# eHub.net
KiCad netlist of a schematic drawn in Altium Designer
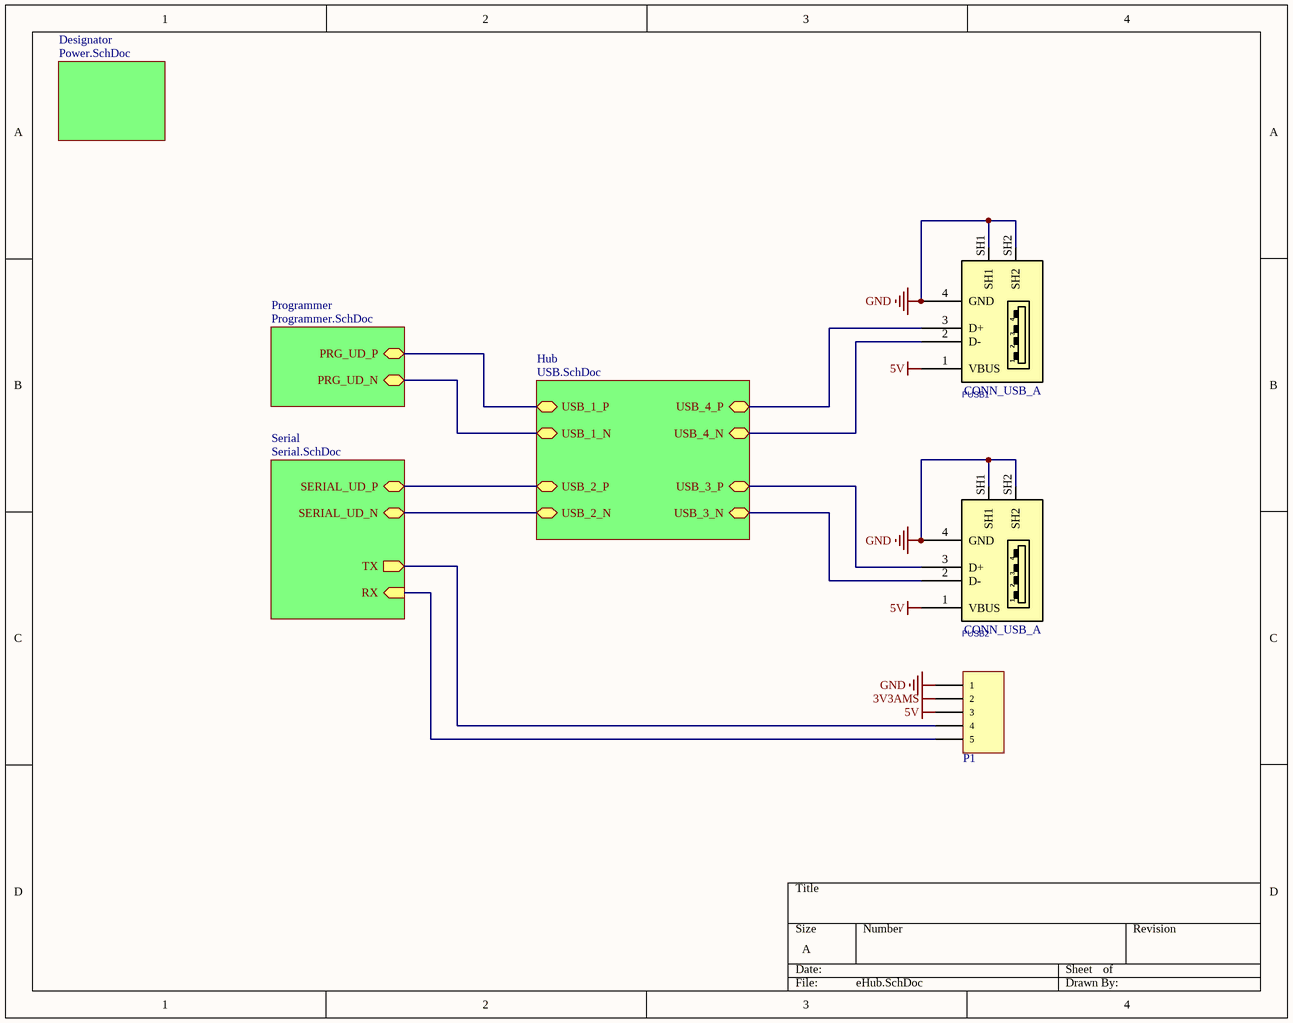
[diagram p0: eHub.SchDoc]

(export (version "E")
  (design (tool "Eeschema 10.0.6"))
  (components
    (comp (ref "P1")
      (value "Header, 5-Pin")
      (footprint "HDR1X5")
      (fields (field (name "PUBLISHER") "Altium Limited"))
      (libsource (lib "Full lib F.kh-V2") (part "Header 5"))
    )
    (comp (ref "PUSB1")
      (value "CONN_USB_A")
      (footprint "USB_A_REC_RA_THD")
      (description "CONN, USB, A, RECEPTACLE, R/A, THD")
      (libsource (lib "Full lib_02") (part "CONN_USB_A_REC_RA_THD"))
    )
    (comp (ref "PUSB2")
      (value "CONN_USB_A")
      (footprint "USB_A_REC_RA_THD")
      (description "CONN, USB, A, RECEPTACLE, R/A, THD")
      (libsource (lib "Full lib_02") (part "CONN_USB_A_REC_RA_THD"))
    )
  )
  (nets
    (net (code "3") (name "/RX") (class "Default")
      (node (ref "P1") (pin "5") (pinfunction "5_5") (pintype "passive"))
    )
    (net (code "6") (name "/TX") (class "Default")
      (node (ref "P1") (pin "4") (pinfunction "4_4") (pintype "passive"))
    )
    (net (code "7") (name "/USB_3_N") (class "Default")
      (node (ref "PUSB2") (pin "2") (pinfunction "D-_2") (pintype "passive"))
    )
    (net (code "8") (name "/USB_3_P") (class "Default")
      (node (ref "PUSB2") (pin "3") (pinfunction "D+_3") (pintype "passive"))
    )
    (net (code "9") (name "/USB_4_N") (class "Default")
      (node (ref "PUSB1") (pin "2") (pinfunction "D-_2") (pintype "passive"))
    )
    (net (code "10") (name "/USB_4_P") (class "Default")
      (node (ref "PUSB1") (pin "3") (pinfunction "D+_3") (pintype "passive"))
    )
    (net (code "11") (name "3V3AMS") (class "Default")
      (node (ref "P1") (pin "2") (pinfunction "2_2") (pintype "passive"))
    )
    (net (code "12") (name "5V") (class "Default")
      (node (ref "P1") (pin "3") (pinfunction "3_3") (pintype "passive"))
      (node (ref "PUSB1") (pin "1") (pinfunction "VBUS_1") (pintype "passive"))
      (node (ref "PUSB2") (pin "1") (pinfunction "VBUS_1") (pintype "passive"))
    )
    (net (code "13") (name "GND") (class "Default")
      (node (ref "P1") (pin "1") (pinfunction "1_1") (pintype "passive"))
      (node (ref "PUSB1") (pin "4") (pinfunction "GND_4") (pintype "passive"))
      (node (ref "PUSB1") (pin "SH1") (pinfunction "SH1_SH1") (pintype "passive"))
      (node (ref "PUSB1") (pin "SH2") (pinfunction "SH2_SH2") (pintype "passive"))
      (node (ref "PUSB2") (pin "4") (pinfunction "GND_4") (pintype "passive"))
      (node (ref "PUSB2") (pin "SH1") (pinfunction "SH1_SH1") (pintype "passive"))
      (node (ref "PUSB2") (pin "SH2") (pinfunction "SH2_SH2") (pintype "passive"))
    )
  )
)
